# LPCB280_-_LIMIT_SWITCHES.net
KiCad netlist of a schematic drawn in Altium Designer
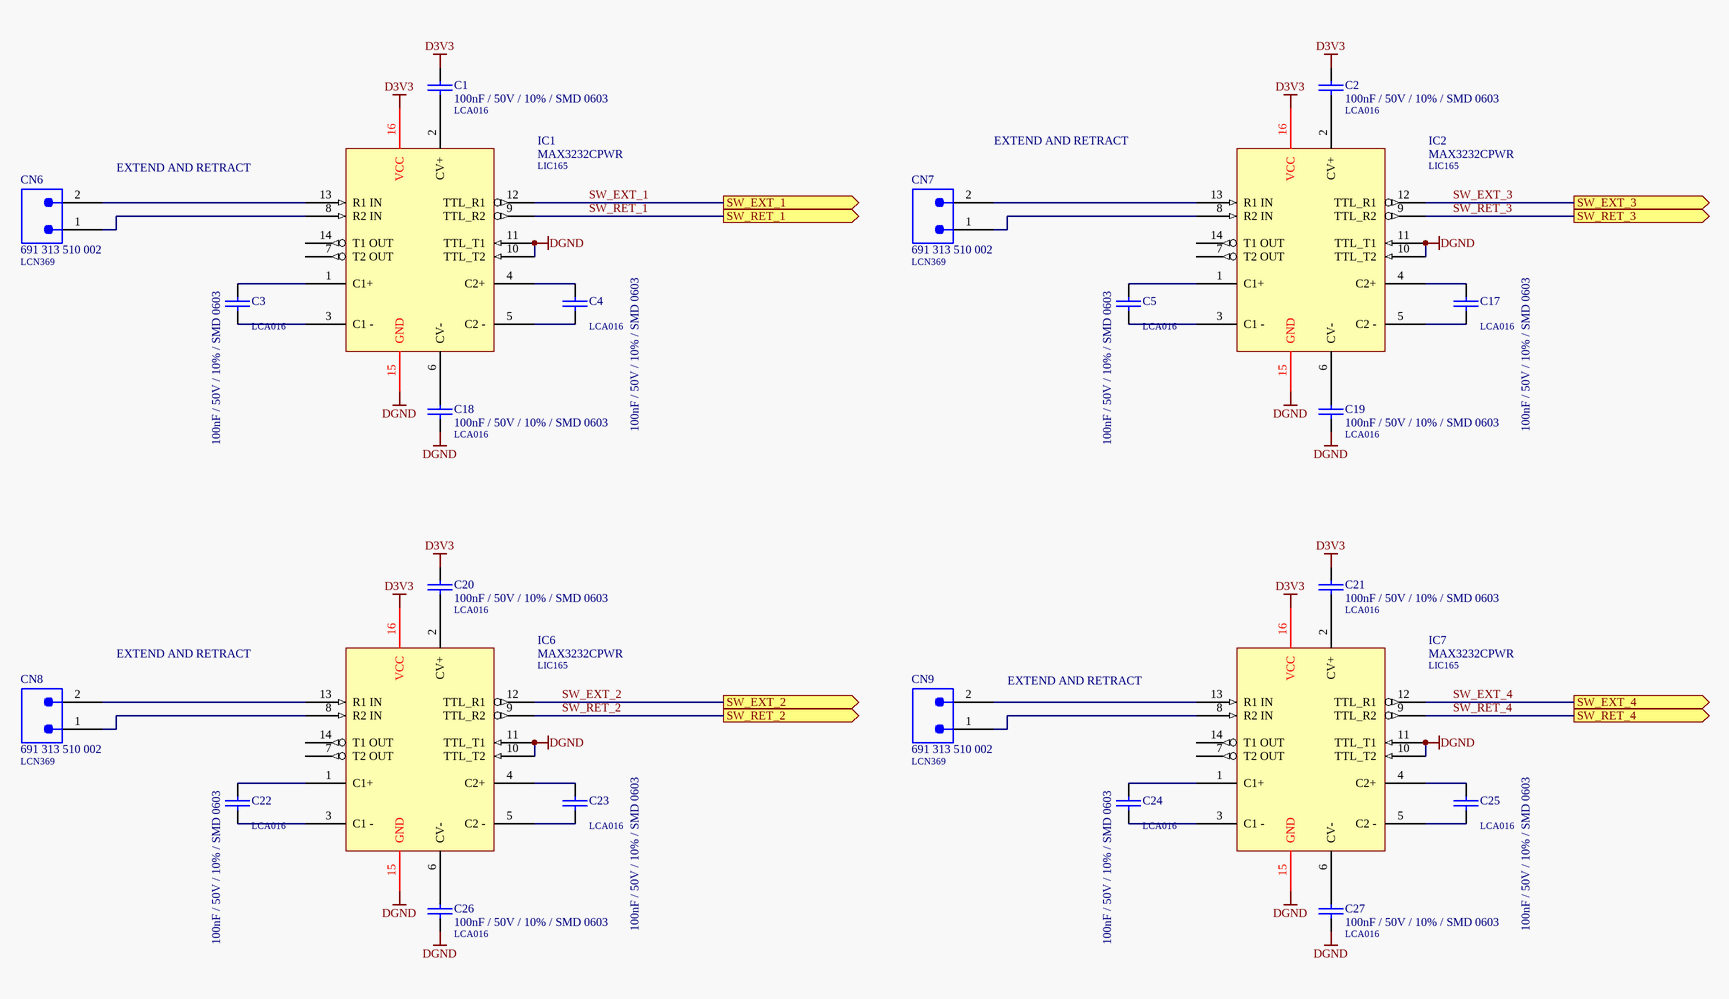
[diagram p0: LPCB280 - LIMIT SWITCHES.SchDoc]

(export (version "E")
  (design (tool "Eeschema 10.0.6"))
  (components
    (comp (ref "C1")
      (value "100nF / 50V / 10% / SMD 0603")
      (footprint "LFP011__CC1608-0603-IPC7351_B")
      (description "Capacitor, Ceramic Chip, 100nF (0.1uF), 50V, 5%, SMD 0603 [LCA016]")
      (fields (field (name "LDL_NUMBER") "LCA016"))
      (libsource (lib "LDL_Capacitors") (part "100nF / 50V / 10% / SMD 0603"))
    )
    (comp (ref "C2")
      (value "100nF / 50V / 10% / SMD 0603")
      (footprint "LFP011__CC1608-0603-IPC7351_B")
      (description "Capacitor, Ceramic Chip, 100nF (0.1uF), 50V, 5%, SMD 0603 [LCA016]")
      (fields (field (name "LDL_NUMBER") "LCA016"))
      (libsource (lib "LDL_Capacitors") (part "100nF / 50V / 10% / SMD 0603"))
    )
    (comp (ref "C3")
      (value "100nF / 50V / 10% / SMD 0603")
      (footprint "LFP011__CC1608-0603-IPC7351_B")
      (description "Capacitor, Ceramic Chip, 100nF (0.1uF), 50V, 5%, SMD 0603 [LCA016]")
      (fields (field (name "LDL_NUMBER") "LCA016"))
      (libsource (lib "LDL_Capacitors") (part "100nF / 50V / 10% / SMD 0603"))
    )
    (comp (ref "C4")
      (value "100nF / 50V / 10% / SMD 0603")
      (footprint "LFP011__CC1608-0603-IPC7351_B")
      (description "Capacitor, Ceramic Chip, 100nF (0.1uF), 50V, 5%, SMD 0603 [LCA016]")
      (fields (field (name "LDL_NUMBER") "LCA016"))
      (libsource (lib "LDL_Capacitors") (part "100nF / 50V / 10% / SMD 0603"))
    )
    (comp (ref "C5")
      (value "100nF / 50V / 10% / SMD 0603")
      (footprint "LFP011__CC1608-0603-IPC7351_B")
      (description "Capacitor, Ceramic Chip, 100nF (0.1uF), 50V, 5%, SMD 0603 [LCA016]")
      (fields (field (name "LDL_NUMBER") "LCA016"))
      (libsource (lib "LDL_Capacitors") (part "100nF / 50V / 10% / SMD 0603"))
    )
    (comp (ref "C17")
      (value "100nF / 50V / 10% / SMD 0603")
      (footprint "LFP011__CC1608-0603-IPC7351_B")
      (description "Capacitor, Ceramic Chip, 100nF (0.1uF), 50V, 5%, SMD 0603 [LCA016]")
      (fields (field (name "LDL_NUMBER") "LCA016"))
      (libsource (lib "LDL_Capacitors") (part "100nF / 50V / 10% / SMD 0603"))
    )
    (comp (ref "C18")
      (value "100nF / 50V / 10% / SMD 0603")
      (footprint "LFP011__CC1608-0603-IPC7351_B")
      (description "Capacitor, Ceramic Chip, 100nF (0.1uF), 50V, 5%, SMD 0603 [LCA016]")
      (fields (field (name "LDL_NUMBER") "LCA016"))
      (libsource (lib "LDL_Capacitors") (part "100nF / 50V / 10% / SMD 0603"))
    )
    (comp (ref "C19")
      (value "100nF / 50V / 10% / SMD 0603")
      (footprint "LFP011__CC1608-0603-IPC7351_B")
      (description "Capacitor, Ceramic Chip, 100nF (0.1uF), 50V, 5%, SMD 0603 [LCA016]")
      (fields (field (name "LDL_NUMBER") "LCA016"))
      (libsource (lib "LDL_Capacitors") (part "100nF / 50V / 10% / SMD 0603"))
    )
    (comp (ref "C20")
      (value "100nF / 50V / 10% / SMD 0603")
      (footprint "LFP011__CC1608-0603-IPC7351_B")
      (description "Capacitor, Ceramic Chip, 100nF (0.1uF), 50V, 5%, SMD 0603 [LCA016]")
      (fields (field (name "LDL_NUMBER") "LCA016"))
      (libsource (lib "LDL_Capacitors") (part "100nF / 50V / 10% / SMD 0603"))
    )
    (comp (ref "C21")
      (value "100nF / 50V / 10% / SMD 0603")
      (footprint "LFP011__CC1608-0603-IPC7351_B")
      (description "Capacitor, Ceramic Chip, 100nF (0.1uF), 50V, 5%, SMD 0603 [LCA016]")
      (fields (field (name "LDL_NUMBER") "LCA016"))
      (libsource (lib "LDL_Capacitors") (part "100nF / 50V / 10% / SMD 0603"))
    )
    (comp (ref "C22")
      (value "100nF / 50V / 10% / SMD 0603")
      (footprint "LFP011__CC1608-0603-IPC7351_B")
      (description "Capacitor, Ceramic Chip, 100nF (0.1uF), 50V, 5%, SMD 0603 [LCA016]")
      (fields (field (name "LDL_NUMBER") "LCA016"))
      (libsource (lib "LDL_Capacitors") (part "100nF / 50V / 10% / SMD 0603"))
    )
    (comp (ref "C23")
      (value "100nF / 50V / 10% / SMD 0603")
      (footprint "LFP011__CC1608-0603-IPC7351_B")
      (description "Capacitor, Ceramic Chip, 100nF (0.1uF), 50V, 5%, SMD 0603 [LCA016]")
      (fields (field (name "LDL_NUMBER") "LCA016"))
      (libsource (lib "LDL_Capacitors") (part "100nF / 50V / 10% / SMD 0603"))
    )
    (comp (ref "C24")
      (value "100nF / 50V / 10% / SMD 0603")
      (footprint "LFP011__CC1608-0603-IPC7351_B")
      (description "Capacitor, Ceramic Chip, 100nF (0.1uF), 50V, 5%, SMD 0603 [LCA016]")
      (fields (field (name "LDL_NUMBER") "LCA016"))
      (libsource (lib "LDL_Capacitors") (part "100nF / 50V / 10% / SMD 0603"))
    )
    (comp (ref "C25")
      (value "100nF / 50V / 10% / SMD 0603")
      (footprint "LFP011__CC1608-0603-IPC7351_B")
      (description "Capacitor, Ceramic Chip, 100nF (0.1uF), 50V, 5%, SMD 0603 [LCA016]")
      (fields (field (name "LDL_NUMBER") "LCA016"))
      (libsource (lib "LDL_Capacitors") (part "100nF / 50V / 10% / SMD 0603"))
    )
    (comp (ref "C26")
      (value "100nF / 50V / 10% / SMD 0603")
      (footprint "LFP011__CC1608-0603-IPC7351_B")
      (description "Capacitor, Ceramic Chip, 100nF (0.1uF), 50V, 5%, SMD 0603 [LCA016]")
      (fields (field (name "LDL_NUMBER") "LCA016"))
      (libsource (lib "LDL_Capacitors") (part "100nF / 50V / 10% / SMD 0603"))
    )
    (comp (ref "C27")
      (value "100nF / 50V / 10% / SMD 0603")
      (footprint "LFP011__CC1608-0603-IPC7351_B")
      (description "Capacitor, Ceramic Chip, 100nF (0.1uF), 50V, 5%, SMD 0603 [LCA016]")
      (fields (field (name "LDL_NUMBER") "LCA016"))
      (libsource (lib "LDL_Capacitors") (part "100nF / 50V / 10% / SMD 0603"))
    )
    (comp (ref "CN6")
      (value "691 313 510 002")
      (footprint "691 313 510 002")
      (description "Connector, Pluggable Terminal Block, 5.08mm, 2 Way, PTH")
      (fields (field (name "LDL_NUMBER") "LCN369"))
      (libsource (lib "LDL_Connectors") (part "691 313 510 002"))
    )
    (comp (ref "CN7")
      (value "691 313 510 002")
      (footprint "691 313 510 002")
      (description "Connector, Pluggable Terminal Block, 5.08mm, 2 Way, PTH")
      (fields (field (name "LDL_NUMBER") "LCN369"))
      (libsource (lib "LDL_Connectors") (part "691 313 510 002"))
    )
    (comp (ref "CN8")
      (value "691 313 510 002")
      (footprint "691 313 510 002")
      (description "Connector, Pluggable Terminal Block, 5.08mm, 2 Way, PTH")
      (fields (field (name "LDL_NUMBER") "LCN369"))
      (libsource (lib "LDL_Connectors") (part "691 313 510 002"))
    )
    (comp (ref "CN9")
      (value "691 313 510 002")
      (footprint "691 313 510 002")
      (description "Connector, Pluggable Terminal Block, 5.08mm, 2 Way, PTH")
      (fields (field (name "LDL_NUMBER") "LCN369"))
      (libsource (lib "LDL_Connectors") (part "691 313 510 002"))
    )
    (comp (ref "IC1")
      (value "MAX3232CPWR")
      (footprint "LFP049__TSSOP-16")
      (description "IC, RS232 Line Driver, 3.3V, SMD TSSOP16 [LIC165]")
      (fields (field (name "LDL_NUMBER") "LIC165"))
      (libsource (lib "LDL_Semiconductors") (part "MAX3232CPWR"))
    )
    (comp (ref "IC2")
      (value "MAX3232CPWR")
      (footprint "LFP049__TSSOP-16")
      (description "IC, RS232 Line Driver, 3.3V, SMD TSSOP16 [LIC165]")
      (fields (field (name "LDL_NUMBER") "LIC165"))
      (libsource (lib "LDL_Semiconductors") (part "MAX3232CPWR"))
    )
    (comp (ref "IC6")
      (value "MAX3232CPWR")
      (footprint "LFP049__TSSOP-16")
      (description "IC, RS232 Line Driver, 3.3V, SMD TSSOP16 [LIC165]")
      (fields (field (name "LDL_NUMBER") "LIC165"))
      (libsource (lib "LDL_Semiconductors") (part "MAX3232CPWR"))
    )
    (comp (ref "IC7")
      (value "MAX3232CPWR")
      (footprint "LFP049__TSSOP-16")
      (description "IC, RS232 Line Driver, 3.3V, SMD TSSOP16 [LIC165]")
      (fields (field (name "LDL_NUMBER") "LIC165"))
      (libsource (lib "LDL_Semiconductors") (part "MAX3232CPWR"))
    )
  )
  (nets
    (net (code "1") (name "/SW_EXT_1") (class "Default")
      (node (ref "IC1") (pin "12") (pinfunction "TTL_R1_12") (pintype "output"))
    )
    (net (code "2") (name "/SW_EXT_2") (class "Default")
      (node (ref "IC6") (pin "12") (pinfunction "TTL_R1_12") (pintype "output"))
    )
    (net (code "3") (name "/SW_EXT_3") (class "Default")
      (node (ref "IC2") (pin "12") (pinfunction "TTL_R1_12") (pintype "output"))
    )
    (net (code "4") (name "/SW_EXT_4") (class "Default")
      (node (ref "IC7") (pin "12") (pinfunction "TTL_R1_12") (pintype "output"))
    )
    (net (code "5") (name "/SW_RET_1") (class "Default")
      (node (ref "IC1") (pin "9") (pinfunction "TTL_R2_9") (pintype "output"))
    )
    (net (code "6") (name "/SW_RET_2") (class "Default")
      (node (ref "IC6") (pin "9") (pinfunction "TTL_R2_9") (pintype "output"))
    )
    (net (code "7") (name "/SW_RET_3") (class "Default")
      (node (ref "IC2") (pin "9") (pinfunction "TTL_R2_9") (pintype "output"))
    )
    (net (code "8") (name "/SW_RET_4") (class "Default")
      (node (ref "IC7") (pin "9") (pinfunction "TTL_R2_9") (pintype "output"))
    )
    (net (code "9") (name "D3V3") (class "Default")
      (node (ref "C1") (pin "1") (pintype "passive"))
      (node (ref "C2") (pin "1") (pintype "passive"))
      (node (ref "C20") (pin "1") (pintype "passive"))
      (node (ref "C21") (pin "1") (pintype "passive"))
      (node (ref "IC1") (pin "16") (pinfunction "VCC_16") (pintype "power_in"))
      (node (ref "IC2") (pin "16") (pinfunction "VCC_16") (pintype "power_in"))
      (node (ref "IC6") (pin "16") (pinfunction "VCC_16") (pintype "power_in"))
      (node (ref "IC7") (pin "16") (pinfunction "VCC_16") (pintype "power_in"))
    )
    (net (code "10") (name "DGND") (class "Default")
      (node (ref "C18") (pin "2") (pintype "passive"))
      (node (ref "C19") (pin "2") (pintype "passive"))
      (node (ref "C26") (pin "2") (pintype "passive"))
      (node (ref "C27") (pin "2") (pintype "passive"))
      (node (ref "IC1") (pin "10") (pinfunction "TTL_T2_10") (pintype "input"))
      (node (ref "IC1") (pin "11") (pinfunction "TTL_T1_11") (pintype "input"))
      (node (ref "IC1") (pin "15") (pinfunction "GND_15") (pintype "power_in"))
      (node (ref "IC2") (pin "10") (pinfunction "TTL_T2_10") (pintype "input"))
      (node (ref "IC2") (pin "11") (pinfunction "TTL_T1_11") (pintype "input"))
      (node (ref "IC2") (pin "15") (pinfunction "GND_15") (pintype "power_in"))
      (node (ref "IC6") (pin "10") (pinfunction "TTL_T2_10") (pintype "input"))
      (node (ref "IC6") (pin "11") (pinfunction "TTL_T1_11") (pintype "input"))
      (node (ref "IC6") (pin "15") (pinfunction "GND_15") (pintype "power_in"))
      (node (ref "IC7") (pin "10") (pinfunction "TTL_T2_10") (pintype "input"))
      (node (ref "IC7") (pin "11") (pinfunction "TTL_T1_11") (pintype "input"))
      (node (ref "IC7") (pin "15") (pinfunction "GND_15") (pintype "power_in"))
    )
    (net (code "11") (name "Net-(IC1-C1+)") (class "Default")
      (node (ref "C3") (pin "1") (pintype "passive"))
      (node (ref "IC1") (pin "1") (pinfunction "C1+_1") (pintype "passive"))
    )
    (net (code "12") (name "Net-(IC1-C1_-)") (class "Default")
      (node (ref "C3") (pin "2") (pintype "passive"))
      (node (ref "IC1") (pin "3") (pinfunction "C1_-_3") (pintype "passive"))
    )
    (net (code "13") (name "Net-(IC1-C2+)") (class "Default")
      (node (ref "C4") (pin "1") (pintype "passive"))
      (node (ref "IC1") (pin "4") (pinfunction "C2+_4") (pintype "passive"))
    )
    (net (code "14") (name "Net-(IC1-C2_-)") (class "Default")
      (node (ref "C4") (pin "2") (pintype "passive"))
      (node (ref "IC1") (pin "5") (pinfunction "C2_-_5") (pintype "passive"))
    )
    (net (code "15") (name "Net-(IC1-CV+)") (class "Default")
      (node (ref "C1") (pin "2") (pintype "passive"))
      (node (ref "IC1") (pin "2") (pinfunction "CV+_2") (pintype "passive"))
    )
    (net (code "16") (name "Net-(IC1-CV-)") (class "Default")
      (node (ref "C18") (pin "1") (pintype "passive"))
      (node (ref "IC1") (pin "6") (pinfunction "CV-_6") (pintype "passive"))
    )
    (net (code "17") (name "Net-(IC1-R1_IN)") (class "Default")
      (node (ref "CN6") (pin "2") (pinfunction "2_2") (pintype "passive"))
      (node (ref "IC1") (pin "13") (pinfunction "R1_IN_13") (pintype "input"))
    )
    (net (code "18") (name "Net-(IC1-R2_IN)") (class "Default")
      (node (ref "CN6") (pin "1") (pinfunction "1_1") (pintype "passive"))
      (node (ref "IC1") (pin "8") (pinfunction "R2_IN_8") (pintype "input"))
    )
    (net (code "19") (name "Net-(IC2-C1+)") (class "Default")
      (node (ref "C5") (pin "1") (pintype "passive"))
      (node (ref "IC2") (pin "1") (pinfunction "C1+_1") (pintype "passive"))
    )
    (net (code "20") (name "Net-(IC2-C1_-)") (class "Default")
      (node (ref "C5") (pin "2") (pintype "passive"))
      (node (ref "IC2") (pin "3") (pinfunction "C1_-_3") (pintype "passive"))
    )
    (net (code "21") (name "Net-(IC2-C2+)") (class "Default")
      (node (ref "C17") (pin "1") (pintype "passive"))
      (node (ref "IC2") (pin "4") (pinfunction "C2+_4") (pintype "passive"))
    )
    (net (code "22") (name "Net-(IC2-C2_-)") (class "Default")
      (node (ref "C17") (pin "2") (pintype "passive"))
      (node (ref "IC2") (pin "5") (pinfunction "C2_-_5") (pintype "passive"))
    )
    (net (code "23") (name "Net-(IC2-CV+)") (class "Default")
      (node (ref "C2") (pin "2") (pintype "passive"))
      (node (ref "IC2") (pin "2") (pinfunction "CV+_2") (pintype "passive"))
    )
    (net (code "24") (name "Net-(IC2-CV-)") (class "Default")
      (node (ref "C19") (pin "1") (pintype "passive"))
      (node (ref "IC2") (pin "6") (pinfunction "CV-_6") (pintype "passive"))
    )
    (net (code "25") (name "Net-(IC2-R1_IN)") (class "Default")
      (node (ref "CN7") (pin "2") (pinfunction "2_2") (pintype "passive"))
      (node (ref "IC2") (pin "13") (pinfunction "R1_IN_13") (pintype "input"))
    )
    (net (code "26") (name "Net-(IC2-R2_IN)") (class "Default")
      (node (ref "CN7") (pin "1") (pinfunction "1_1") (pintype "passive"))
      (node (ref "IC2") (pin "8") (pinfunction "R2_IN_8") (pintype "input"))
    )
    (net (code "27") (name "Net-(IC6-C1+)") (class "Default")
      (node (ref "C22") (pin "1") (pintype "passive"))
      (node (ref "IC6") (pin "1") (pinfunction "C1+_1") (pintype "passive"))
    )
    (net (code "28") (name "Net-(IC6-C1_-)") (class "Default")
      (node (ref "C22") (pin "2") (pintype "passive"))
      (node (ref "IC6") (pin "3") (pinfunction "C1_-_3") (pintype "passive"))
    )
    (net (code "29") (name "Net-(IC6-C2+)") (class "Default")
      (node (ref "C23") (pin "1") (pintype "passive"))
      (node (ref "IC6") (pin "4") (pinfunction "C2+_4") (pintype "passive"))
    )
    (net (code "30") (name "Net-(IC6-C2_-)") (class "Default")
      (node (ref "C23") (pin "2") (pintype "passive"))
      (node (ref "IC6") (pin "5") (pinfunction "C2_-_5") (pintype "passive"))
    )
    (net (code "31") (name "Net-(IC6-CV+)") (class "Default")
      (node (ref "C20") (pin "2") (pintype "passive"))
      (node (ref "IC6") (pin "2") (pinfunction "CV+_2") (pintype "passive"))
    )
    (net (code "32") (name "Net-(IC6-CV-)") (class "Default")
      (node (ref "C26") (pin "1") (pintype "passive"))
      (node (ref "IC6") (pin "6") (pinfunction "CV-_6") (pintype "passive"))
    )
    (net (code "33") (name "Net-(IC6-R1_IN)") (class "Default")
      (node (ref "CN8") (pin "2") (pinfunction "2_2") (pintype "passive"))
      (node (ref "IC6") (pin "13") (pinfunction "R1_IN_13") (pintype "input"))
    )
    (net (code "34") (name "Net-(IC6-R2_IN)") (class "Default")
      (node (ref "CN8") (pin "1") (pinfunction "1_1") (pintype "passive"))
      (node (ref "IC6") (pin "8") (pinfunction "R2_IN_8") (pintype "input"))
    )
    (net (code "35") (name "Net-(IC7-C1+)") (class "Default")
      (node (ref "C24") (pin "1") (pintype "passive"))
      (node (ref "IC7") (pin "1") (pinfunction "C1+_1") (pintype "passive"))
    )
    (net (code "36") (name "Net-(IC7-C1_-)") (class "Default")
      (node (ref "C24") (pin "2") (pintype "passive"))
      (node (ref "IC7") (pin "3") (pinfunction "C1_-_3") (pintype "passive"))
    )
    (net (code "37") (name "Net-(IC7-C2+)") (class "Default")
      (node (ref "C25") (pin "1") (pintype "passive"))
      (node (ref "IC7") (pin "4") (pinfunction "C2+_4") (pintype "passive"))
    )
    (net (code "38") (name "Net-(IC7-C2_-)") (class "Default")
      (node (ref "C25") (pin "2") (pintype "passive"))
      (node (ref "IC7") (pin "5") (pinfunction "C2_-_5") (pintype "passive"))
    )
    (net (code "39") (name "Net-(IC7-CV+)") (class "Default")
      (node (ref "C21") (pin "2") (pintype "passive"))
      (node (ref "IC7") (pin "2") (pinfunction "CV+_2") (pintype "passive"))
    )
    (net (code "40") (name "Net-(IC7-CV-)") (class "Default")
      (node (ref "C27") (pin "1") (pintype "passive"))
      (node (ref "IC7") (pin "6") (pinfunction "CV-_6") (pintype "passive"))
    )
    (net (code "41") (name "Net-(IC7-R1_IN)") (class "Default")
      (node (ref "CN9") (pin "2") (pinfunction "2_2") (pintype "passive"))
      (node (ref "IC7") (pin "13") (pinfunction "R1_IN_13") (pintype "input"))
    )
    (net (code "42") (name "Net-(IC7-R2_IN)") (class "Default")
      (node (ref "CN9") (pin "1") (pinfunction "1_1") (pintype "passive"))
      (node (ref "IC7") (pin "8") (pinfunction "R2_IN_8") (pintype "input"))
    )
    (net (code "43") (name "unconnected-(IC1-T1_OUT-Pad14)") (class "Default")
      (node (ref "IC1") (pin "14") (pinfunction "T1_OUT_14") (pintype "output"))
    )
    (net (code "44") (name "unconnected-(IC1-T2_OUT-Pad7)") (class "Default")
      (node (ref "IC1") (pin "7") (pinfunction "T2_OUT_7") (pintype "output"))
    )
    (net (code "45") (name "unconnected-(IC2-T1_OUT-Pad14)") (class "Default")
      (node (ref "IC2") (pin "14") (pinfunction "T1_OUT_14") (pintype "output"))
    )
    (net (code "46") (name "unconnected-(IC2-T2_OUT-Pad7)") (class "Default")
      (node (ref "IC2") (pin "7") (pinfunction "T2_OUT_7") (pintype "output"))
    )
    (net (code "47") (name "unconnected-(IC6-T1_OUT-Pad14)") (class "Default")
      (node (ref "IC6") (pin "14") (pinfunction "T1_OUT_14") (pintype "output"))
    )
    (net (code "48") (name "unconnected-(IC6-T2_OUT-Pad7)") (class "Default")
      (node (ref "IC6") (pin "7") (pinfunction "T2_OUT_7") (pintype "output"))
    )
    (net (code "49") (name "unconnected-(IC7-T1_OUT-Pad14)") (class "Default")
      (node (ref "IC7") (pin "14") (pinfunction "T1_OUT_14") (pintype "output"))
    )
    (net (code "50") (name "unconnected-(IC7-T2_OUT-Pad7)") (class "Default")
      (node (ref "IC7") (pin "7") (pinfunction "T2_OUT_7") (pintype "output"))
    )
  )
)
